# brightness_control.net
KiCad netlist of a schematic drawn in EAGLE
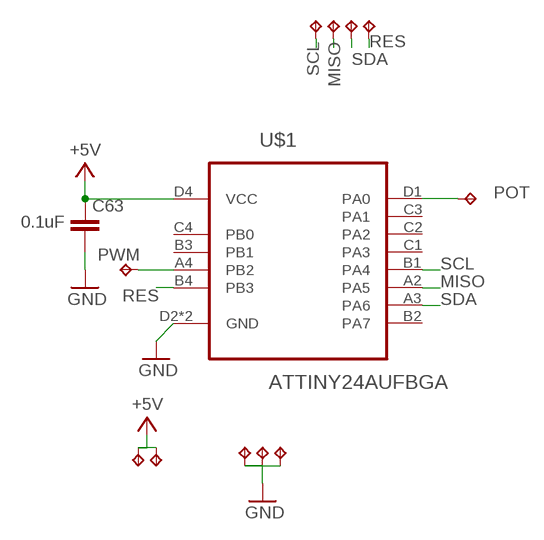
[diagram p0: schematic, sheet 1]

(export (version "E")
  (design (tool "Eeschema 10.0.6"))
  (components
    (comp (ref "C63")
      (value "0.1uF")
      (footprint "eagle-import:C0402")
      (libsource (lib "eagle-import") (part "C-USC0402"))
    )
    (comp (ref "TP1")
      (value "TPTP12R")
      (footprint "eagle-import:TP12R")
      (libsource (lib "eagle-import") (part "TPTP12R"))
    )
    (comp (ref "TP3")
      (value "TPTP12R")
      (footprint "eagle-import:TP12R")
      (libsource (lib "eagle-import") (part "TPTP12R"))
    )
    (comp (ref "TP4")
      (value "TPTP12R")
      (footprint "eagle-import:TP12R")
      (libsource (lib "eagle-import") (part "TPTP12R"))
    )
    (comp (ref "TP5")
      (value "TPTP12R")
      (footprint "eagle-import:TP12R")
      (libsource (lib "eagle-import") (part "TPTP12R"))
    )
    (comp (ref "TP6")
      (value "TPTP12R")
      (footprint "eagle-import:TP12R")
      (libsource (lib "eagle-import") (part "TPTP12R"))
    )
    (comp (ref "TP7")
      (value "TPTP12R")
      (footprint "eagle-import:TP12R")
      (libsource (lib "eagle-import") (part "TPTP12R"))
    )
    (comp (ref "TP8")
      (value "TPTP12R")
      (footprint "eagle-import:TP12R")
      (libsource (lib "eagle-import") (part "TPTP12R"))
    )
    (comp (ref "TP10")
      (value "TPTP12R")
      (footprint "eagle-import:TP12R")
      (libsource (lib "eagle-import") (part "TPTP12R"))
    )
    (comp (ref "TP11")
      (value "TPTP12R")
      (footprint "eagle-import:TP12R")
      (libsource (lib "eagle-import") (part "TPTP12R"))
    )
    (comp (ref "TP12")
      (value "TPTP12R")
      (footprint "eagle-import:TP12R")
      (libsource (lib "eagle-import") (part "TPTP12R"))
    )
    (comp (ref "TP13")
      (value "TPTP12R")
      (footprint "eagle-import:TP12R")
      (libsource (lib "eagle-import") (part "TPTP12R"))
    )
    (comp (ref "U$1")
      (value "ATTINY24AUFBGA")
      (footprint "eagle-import:UFBGA-15")
      (libsource (lib "eagle-import") (part "ATTINY24AUFBGA"))
    )
  )
  (nets
    (net (code "1") (name "+5V") (class "Default")
      (node (ref "C63") (pin "1") (pinfunction "1_1") (pintype "passive"))
      (node (ref "TP3") (pin "TP") (pinfunction "TP_TP") (pintype "input"))
      (node (ref "TP4") (pin "TP") (pinfunction "TP_TP") (pintype "input"))
      (node (ref "U$1") (pin "D4") (pinfunction "VCC_D4") (pintype "power_in"))
    )
    (net (code "2") (name "/MISO") (class "Default")
      (node (ref "TP11") (pin "TP") (pinfunction "TP_TP") (pintype "input"))
      (node (ref "U$1") (pin "A2") (pinfunction "PA5_A2") (pintype "bidirectional"))
    )
    (net (code "3") (name "/POT") (class "Default")
      (node (ref "TP7") (pin "TP") (pinfunction "TP_TP") (pintype "input"))
      (node (ref "U$1") (pin "D1") (pinfunction "PA0_D1") (pintype "bidirectional"))
    )
    (net (code "4") (name "/PWM") (class "Default")
      (node (ref "TP8") (pin "TP") (pinfunction "TP_TP") (pintype "input"))
      (node (ref "U$1") (pin "A4") (pinfunction "PB2_A4") (pintype "bidirectional"))
    )
    (net (code "5") (name "/RES") (class "Default")
      (node (ref "TP13") (pin "TP") (pinfunction "TP_TP") (pintype "input"))
      (node (ref "U$1") (pin "B4") (pinfunction "PB3_B4") (pintype "bidirectional"))
    )
    (net (code "6") (name "/SCL") (class "Default")
      (node (ref "TP10") (pin "TP") (pinfunction "TP_TP") (pintype "input"))
      (node (ref "U$1") (pin "B1") (pinfunction "PA4_B1") (pintype "bidirectional"))
    )
    (net (code "7") (name "/SDA") (class "Default")
      (node (ref "TP12") (pin "TP") (pinfunction "TP_TP") (pintype "input"))
      (node (ref "U$1") (pin "A3") (pinfunction "PA6_A3") (pintype "bidirectional"))
    )
    (net (code "8") (name "GND") (class "Default")
      (node (ref "C63") (pin "2") (pinfunction "2_2") (pintype "passive"))
      (node (ref "TP1") (pin "TP") (pinfunction "TP_TP") (pintype "input"))
      (node (ref "TP5") (pin "TP") (pinfunction "TP_TP") (pintype "input"))
      (node (ref "TP6") (pin "TP") (pinfunction "TP_TP") (pintype "input"))
      (node (ref "U$1") (pin "D2") (pinfunction "GND_D2") (pintype "power_in"))
      (node (ref "U$1") (pin "D3") (pinfunction "GND_D3") (pintype "power_in"))
    )
    (net (code "9") (name "unconnected-(U$1-PA1-PadC3)") (class "Default")
      (node (ref "U$1") (pin "C3") (pinfunction "PA1_C3") (pintype "bidirectional"))
    )
    (net (code "10") (name "unconnected-(U$1-PA2-PadC2)") (class "Default")
      (node (ref "U$1") (pin "C2") (pinfunction "PA2_C2") (pintype "bidirectional"))
    )
    (net (code "11") (name "unconnected-(U$1-PA3-PadC1)") (class "Default")
      (node (ref "U$1") (pin "C1") (pinfunction "PA3_C1") (pintype "bidirectional"))
    )
    (net (code "12") (name "unconnected-(U$1-PA7-PadB2)") (class "Default")
      (node (ref "U$1") (pin "B2") (pinfunction "PA7_B2") (pintype "bidirectional"))
    )
    (net (code "13") (name "unconnected-(U$1-PB0-PadC4)") (class "Default")
      (node (ref "U$1") (pin "C4") (pinfunction "PB0_C4") (pintype "bidirectional"))
    )
    (net (code "14") (name "unconnected-(U$1-PB1-PadB3)") (class "Default")
      (node (ref "U$1") (pin "B3") (pinfunction "PB1_B3") (pintype "bidirectional"))
    )
  )
)
